# Sheet1.net
KiCad netlist of a schematic drawn in Altium Designer
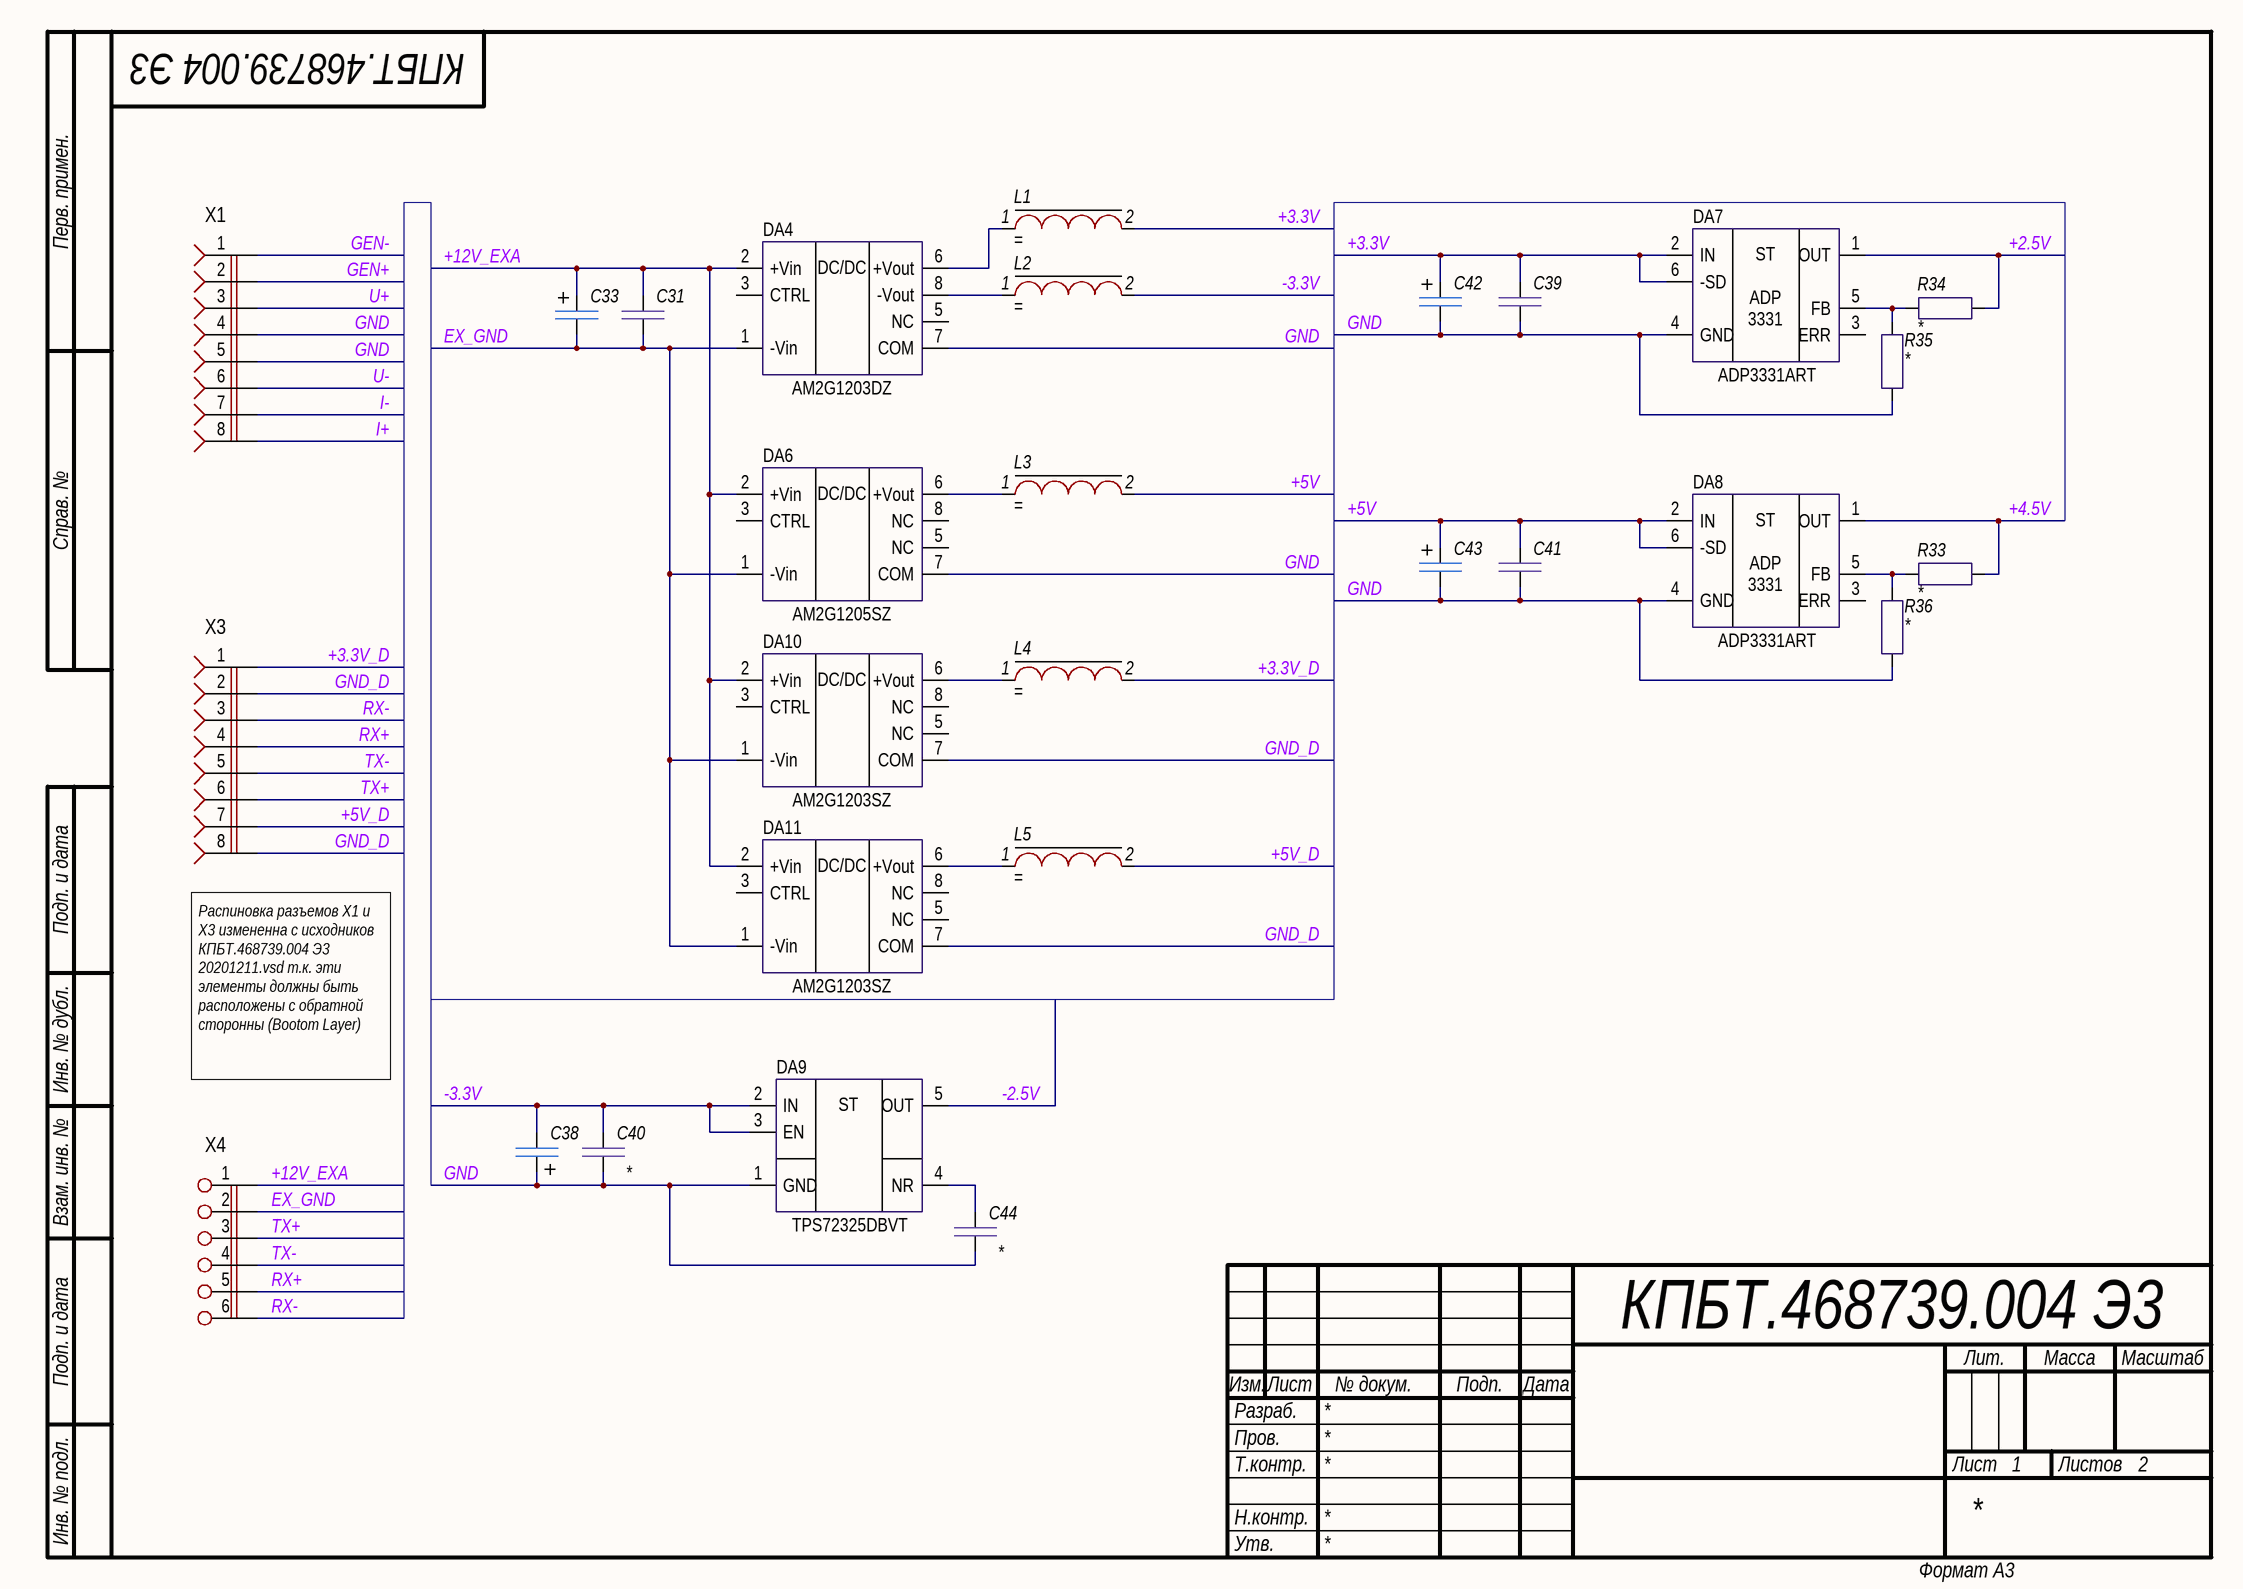
[diagram p0: Sheet1.SchDoc]

(export (version "E")
  (design (tool "Eeschema 10.0.6"))
  (components
    (comp (ref "C31")
      (value "*")
      (footprint "CAP:0805")
      (fields (field (name "PART NUMBER") "Capacitor 0805"))
      (libsource (lib "LibDb") (part "CAP{colon}0805"))
    )
    (comp (ref "C33")
      (value "~")
      (footprint "CAPT: tepy B")
      (fields (field (name "PART NUMBER") "CAPT: tepy B"))
      (libsource (lib "LibDb") (part "CAPT{colon} tepy B"))
    )
    (comp (ref "C38")
      (value "~")
      (footprint "CAPT: tepy B")
      (fields (field (name "PART NUMBER") "CAPT: tepy B"))
      (libsource (lib "LibDb") (part "CAPT{colon} tepy B"))
    )
    (comp (ref "C39")
      (value "*")
      (footprint "CAP:0805")
      (fields (field (name "PART NUMBER") "Capacitor 0805"))
      (libsource (lib "LibDb") (part "CAP{colon}0805"))
    )
    (comp (ref "C40")
      (value "*")
      (footprint "CAP:0805")
      (fields (field (name "PART NUMBER") "Capacitor 0805"))
      (libsource (lib "") (part "CAP{colon}0805_1"))
    )
    (comp (ref "C41")
      (value "*")
      (footprint "CAP:0805")
      (fields (field (name "PART NUMBER") "Capacitor 0805"))
      (libsource (lib "LibDb") (part "CAP{colon}0805"))
    )
    (comp (ref "C42")
      (value "~")
      (footprint "CAPT: tepy B")
      (fields (field (name "PART NUMBER") "CAPT: tepy B"))
      (libsource (lib "LibDb") (part "CAPT{colon} tepy B"))
    )
    (comp (ref "C43")
      (value "~")
      (footprint "CAPT: tepy B")
      (fields (field (name "PART NUMBER") "CAPT: tepy B"))
      (libsource (lib "LibDb") (part "CAPT{colon} tepy B"))
    )
    (comp (ref "C44")
      (value "*")
      (footprint "CAP:0805")
      (fields (field (name "PART NUMBER") "Capacitor 0805"))
      (libsource (lib "LibDb") (part "CAP{colon}0805"))
    )
    (comp (ref "DA4") (value "AM2G1203DZ") (footprint "SIP-8") (libsource (lib "LibDb") (part "AM2G1203DZ")))
    (comp (ref "DA6") (value "AM2G1205SZ") (footprint "SIP-8") (libsource (lib "LibDb") (part "AM2G1205SZ")))
    (comp (ref "DA7")
      (value "ADP3331ART")
      (footprint "SOT23-6")
      (libsource (lib "LibDb") (part "ADP3331ART"))
    )
    (comp (ref "DA8")
      (value "ADP3331ART")
      (footprint "SOT23-6")
      (libsource (lib "LibDb") (part "ADP3331ART"))
    )
    (comp (ref "DA9")
      (value "TPS72325DBVT")
      (footprint "SOT23-5")
      (libsource (lib "LibDb") (part "TPS72325DBVT"))
    )
    (comp (ref "DA10") (value "AM2G1203SZ") (footprint "SIP-8") (libsource (lib "LibDb") (part "AM2G1203SZ")))
    (comp (ref "DA11") (value "AM2G1203SZ") (footprint "SIP-8") (libsource (lib "LibDb") (part "AM2G1203SZ")))
    (comp (ref "L1")
      (value "~")
      (footprint "LQH55DNxxM03")
      (fields (field (name "PART NUMBER") "LQH55DN101M03"))
      (libsource (lib "LibDb") (part "LQH55DN101M03"))
    )
    (comp (ref "L2")
      (value "~")
      (footprint "LQH55DNxxM03")
      (fields (field (name "PART NUMBER") "LQH55DN101M03"))
      (libsource (lib "LibDb") (part "LQH55DN101M03"))
    )
    (comp (ref "L3")
      (value "~")
      (footprint "LQH55DNxxM03")
      (fields (field (name "PART NUMBER") "LQH55DN101M03"))
      (libsource (lib "LibDb") (part "LQH55DN101M03"))
    )
    (comp (ref "L4")
      (value "~")
      (footprint "LQH55DNxxM03")
      (fields (field (name "PART NUMBER") "LQH55DN101M03"))
      (libsource (lib "LibDb") (part "LQH55DN101M03"))
    )
    (comp (ref "L5")
      (value "~")
      (footprint "LQH55DNxxM03")
      (fields (field (name "PART NUMBER") "LQH55DN101M03"))
      (libsource (lib "LibDb") (part "LQH55DN101M03"))
    )
    (comp (ref "R33")
      (value "*")
      (footprint "RES:0805")
      (fields (field (name "PART NUMBER") "Resistor 0805"))
      (libsource (lib "LibDb") (part "RES{colon}0805"))
    )
    (comp (ref "R34")
      (value "*")
      (footprint "RES:0805")
      (fields (field (name "PART NUMBER") "Resistor 0805"))
      (libsource (lib "LibDb") (part "RES{colon}0805"))
    )
    (comp (ref "R35")
      (value "*")
      (footprint "RES:0805")
      (fields (field (name "PART NUMBER") "Resistor 0805"))
      (libsource (lib "LibDb") (part "RES{colon}0805"))
    )
    (comp (ref "R36")
      (value "*")
      (footprint "RES:0805")
      (fields (field (name "PART NUMBER") "Resistor 0805"))
      (libsource (lib "") (part "RES{colon}0805_1"))
    )
    (comp (ref "X1") (value "PBS-8") (footprint "PBS-8") (libsource (lib "LibDb") (part "PBS-8")))
    (comp (ref "X3") (value "PBS-8") (footprint "PBS-8") (libsource (lib "LibDb") (part "PBS-8")))
    (comp (ref "X4")
      (value "~")
      (footprint "2EDGVM-5.0-06P-14-00AH")
      (fields (field (name "PART NUMBER") "2EDGxx-5.0-06P-14-00AH"))
      (libsource (lib "LibDb") (part "2EDGxx-5.0-06P-14-00AH"))
    )
  )
  (nets
    (net (code "1") (name "/+2.5V") (class "Default")
      (node (ref "DA7") (pin "1") (pinfunction "OUT_1") (pintype "passive"))
      (node (ref "R34") (pin "2") (pintype "passive"))
    )
    (net (code "2") (name "/+3.3V") (class "Default")
      (node (ref "C39") (pin "1") (pintype "passive"))
      (node (ref "C42") (pin "2") (pintype "passive"))
      (node (ref "DA7") (pin "2") (pinfunction "IN_2") (pintype "passive"))
      (node (ref "DA7") (pin "6") (pinfunction "-SD_6") (pintype "passive"))
      (node (ref "L1") (pin "2") (pinfunction "2_2") (pintype "passive"))
    )
    (net (code "3") (name "/+3.3V_D") (class "Default")
      (node (ref "L4") (pin "2") (pinfunction "2_2") (pintype "passive"))
      (node (ref "X3") (pin "1") (pintype "passive"))
    )
    (net (code "4") (name "/+4.5V") (class "Default")
      (node (ref "DA8") (pin "1") (pinfunction "OUT_1") (pintype "passive"))
      (node (ref "R33") (pin "2") (pintype "passive"))
    )
    (net (code "5") (name "/+5V") (class "Default")
      (node (ref "C41") (pin "1") (pintype "passive"))
      (node (ref "C43") (pin "2") (pintype "passive"))
      (node (ref "DA8") (pin "2") (pinfunction "IN_2") (pintype "passive"))
      (node (ref "DA8") (pin "6") (pinfunction "-SD_6") (pintype "passive"))
      (node (ref "L3") (pin "2") (pinfunction "2_2") (pintype "passive"))
    )
    (net (code "6") (name "/+5V_D") (class "Default")
      (node (ref "L5") (pin "2") (pinfunction "2_2") (pintype "passive"))
      (node (ref "X3") (pin "7") (pintype "passive"))
    )
    (net (code "7") (name "/+12V_EXA") (class "Default")
      (node (ref "C31") (pin "1") (pintype "passive"))
      (node (ref "C33") (pin "2") (pintype "passive"))
      (node (ref "DA10") (pin "2") (pinfunction "+Vin_2") (pintype "passive"))
      (node (ref "DA11") (pin "2") (pinfunction "+Vin_2") (pintype "passive"))
      (node (ref "DA4") (pin "2") (pinfunction "+Vin_2") (pintype "passive"))
      (node (ref "DA6") (pin "2") (pinfunction "+Vin_2") (pintype "passive"))
      (node (ref "X4") (pin "1") (pintype "passive"))
    )
    (net (code "8") (name "/-2.5V") (class "Default")
      (node (ref "DA9") (pin "5") (pinfunction "OUT_5") (pintype "passive"))
    )
    (net (code "9") (name "/-3.3V") (class "Default")
      (node (ref "C38") (pin "1") (pintype "passive"))
      (node (ref "C40") (pin "2") (pintype "passive"))
      (node (ref "DA9") (pin "2") (pinfunction "IN_2") (pintype "passive"))
      (node (ref "DA9") (pin "3") (pinfunction "EN_3") (pintype "passive"))
      (node (ref "L2") (pin "2") (pinfunction "2_2") (pintype "passive"))
    )
    (net (code "10") (name "/EX_GND") (class "Default")
      (node (ref "C31") (pin "2") (pintype "passive"))
      (node (ref "C33") (pin "1") (pintype "passive"))
      (node (ref "DA10") (pin "1") (pinfunction "-Vin_1") (pintype "passive"))
      (node (ref "DA11") (pin "1") (pinfunction "-Vin_1") (pintype "passive"))
      (node (ref "DA4") (pin "1") (pinfunction "-Vin_1") (pintype "passive"))
      (node (ref "DA6") (pin "1") (pinfunction "-Vin_1") (pintype "passive"))
      (node (ref "X4") (pin "2") (pintype "passive"))
    )
    (net (code "11") (name "/GEN+") (class "Default") (node (ref "X1") (pin "2") (pintype "passive")))
    (net (code "12") (name "/GEN-") (class "Default") (node (ref "X1") (pin "1") (pintype "passive")))
    (net (code "13") (name "/GND") (class "Default")
      (node (ref "C38") (pin "2") (pintype "passive"))
      (node (ref "C39") (pin "2") (pintype "passive"))
      (node (ref "C40") (pin "1") (pintype "passive"))
      (node (ref "C41") (pin "2") (pintype "passive"))
      (node (ref "C42") (pin "1") (pintype "passive"))
      (node (ref "C43") (pin "1") (pintype "passive"))
      (node (ref "C44") (pin "2") (pintype "passive"))
      (node (ref "DA4") (pin "7") (pinfunction "COM_7") (pintype "passive"))
      (node (ref "DA6") (pin "7") (pinfunction "COM_7") (pintype "passive"))
      (node (ref "DA7") (pin "4") (pinfunction "GND_4") (pintype "passive"))
      (node (ref "DA8") (pin "4") (pinfunction "GND_4") (pintype "passive"))
      (node (ref "DA9") (pin "1") (pinfunction "GND_1") (pintype "passive"))
      (node (ref "R35") (pin "2") (pintype "passive"))
      (node (ref "R36") (pin "2") (pintype "passive"))
      (node (ref "X1") (pin "4") (pintype "passive"))
      (node (ref "X1") (pin "5") (pintype "passive"))
    )
    (net (code "14") (name "/GND_D") (class "Default")
      (node (ref "DA10") (pin "7") (pinfunction "COM_7") (pintype "passive"))
      (node (ref "DA11") (pin "7") (pinfunction "COM_7") (pintype "passive"))
      (node (ref "X3") (pin "2") (pintype "passive"))
      (node (ref "X3") (pin "8") (pintype "passive"))
    )
    (net (code "15") (name "/I+") (class "Default") (node (ref "X1") (pin "8") (pintype "passive")))
    (net (code "16") (name "/I-") (class "Default") (node (ref "X1") (pin "7") (pintype "passive")))
    (net (code "17") (name "/RX+") (class "Default")
      (node (ref "X3") (pin "4") (pintype "passive"))
      (node (ref "X4") (pin "5") (pintype "passive"))
    )
    (net (code "18") (name "/RX-") (class "Default")
      (node (ref "X3") (pin "3") (pintype "passive"))
      (node (ref "X4") (pin "6") (pintype "passive"))
    )
    (net (code "19") (name "/TX+") (class "Default")
      (node (ref "X3") (pin "6") (pintype "passive"))
      (node (ref "X4") (pin "3") (pintype "passive"))
    )
    (net (code "20") (name "/TX-") (class "Default")
      (node (ref "X3") (pin "5") (pintype "passive"))
      (node (ref "X4") (pin "4") (pintype "passive"))
    )
    (net (code "21") (name "/U+") (class "Default") (node (ref "X1") (pin "3") (pintype "passive")))
    (net (code "22") (name "/U-") (class "Default") (node (ref "X1") (pin "6") (pintype "passive")))
    (net (code "23") (name "Net-(DA4-+Vout)") (class "Default")
      (node (ref "DA4") (pin "6") (pinfunction "+Vout_6") (pintype "passive"))
      (node (ref "L1") (pin "1") (pinfunction "1_1") (pintype "passive"))
    )
    (net (code "24") (name "Net-(DA4--Vout)") (class "Default")
      (node (ref "DA4") (pin "8") (pinfunction "-Vout_8") (pintype "passive"))
      (node (ref "L2") (pin "1") (pinfunction "1_1") (pintype "passive"))
    )
    (net (code "25") (name "Net-(DA6-+Vout)") (class "Default")
      (node (ref "DA6") (pin "6") (pinfunction "+Vout_6") (pintype "passive"))
      (node (ref "L3") (pin "1") (pinfunction "1_1") (pintype "passive"))
    )
    (net (code "26") (name "Net-(DA7-FB)") (class "Default")
      (node (ref "DA7") (pin "5") (pinfunction "FB_5") (pintype "passive"))
      (node (ref "R34") (pin "1") (pintype "passive"))
      (node (ref "R35") (pin "1") (pintype "passive"))
    )
    (net (code "27") (name "Net-(DA8-FB)") (class "Default")
      (node (ref "DA8") (pin "5") (pinfunction "FB_5") (pintype "passive"))
      (node (ref "R33") (pin "1") (pintype "passive"))
      (node (ref "R36") (pin "1") (pintype "passive"))
    )
    (net (code "28") (name "Net-(DA9-NR)") (class "Default")
      (node (ref "C44") (pin "1") (pintype "passive"))
      (node (ref "DA9") (pin "4") (pinfunction "NR_4") (pintype "passive"))
    )
    (net (code "29") (name "Net-(DA10-+Vout)") (class "Default")
      (node (ref "DA10") (pin "6") (pinfunction "+Vout_6") (pintype "passive"))
      (node (ref "L4") (pin "1") (pinfunction "1_1") (pintype "passive"))
    )
    (net (code "30") (name "Net-(DA11-+Vout)") (class "Default")
      (node (ref "DA11") (pin "6") (pinfunction "+Vout_6") (pintype "passive"))
      (node (ref "L5") (pin "1") (pinfunction "1_1") (pintype "passive"))
    )
    (net (code "31") (name "unconnected-(DA4-CTRL-Pad3)") (class "Default")
      (node (ref "DA4") (pin "3") (pinfunction "CTRL_3") (pintype "passive"))
    )
    (net (code "32") (name "unconnected-(DA4-NC-Pad5)") (class "Default")
      (node (ref "DA4") (pin "5") (pinfunction "NC_5") (pintype "passive"))
    )
    (net (code "33") (name "unconnected-(DA6-CTRL-Pad3)") (class "Default")
      (node (ref "DA6") (pin "3") (pinfunction "CTRL_3") (pintype "passive"))
    )
    (net (code "34") (name "unconnected-(DA6-NC-Pad5)") (class "Default")
      (node (ref "DA6") (pin "5") (pinfunction "NC_5") (pintype "passive"))
    )
    (net (code "35") (name "unconnected-(DA6-NC-Pad8)") (class "Default")
      (node (ref "DA6") (pin "8") (pinfunction "NC_8") (pintype "passive"))
    )
    (net (code "36") (name "unconnected-(DA7-ERR-Pad3)") (class "Default")
      (node (ref "DA7") (pin "3") (pinfunction "ERR_3") (pintype "passive"))
    )
    (net (code "37") (name "unconnected-(DA8-ERR-Pad3)") (class "Default")
      (node (ref "DA8") (pin "3") (pinfunction "ERR_3") (pintype "passive"))
    )
    (net (code "38") (name "unconnected-(DA10-CTRL-Pad3)") (class "Default")
      (node (ref "DA10") (pin "3") (pinfunction "CTRL_3") (pintype "passive"))
    )
    (net (code "39") (name "unconnected-(DA10-NC-Pad5)") (class "Default")
      (node (ref "DA10") (pin "5") (pinfunction "NC_5") (pintype "passive"))
    )
    (net (code "40") (name "unconnected-(DA10-NC-Pad8)") (class "Default")
      (node (ref "DA10") (pin "8") (pinfunction "NC_8") (pintype "passive"))
    )
    (net (code "41") (name "unconnected-(DA11-CTRL-Pad3)") (class "Default")
      (node (ref "DA11") (pin "3") (pinfunction "CTRL_3") (pintype "passive"))
    )
    (net (code "42") (name "unconnected-(DA11-NC-Pad5)") (class "Default")
      (node (ref "DA11") (pin "5") (pinfunction "NC_5") (pintype "passive"))
    )
    (net (code "43") (name "unconnected-(DA11-NC-Pad8)") (class "Default")
      (node (ref "DA11") (pin "8") (pinfunction "NC_8") (pintype "passive"))
    )
  )
)
